# NLQHD-SATA_Front_Panel_Rev1.net
KiCad netlist of a schematic drawn in EAGLE
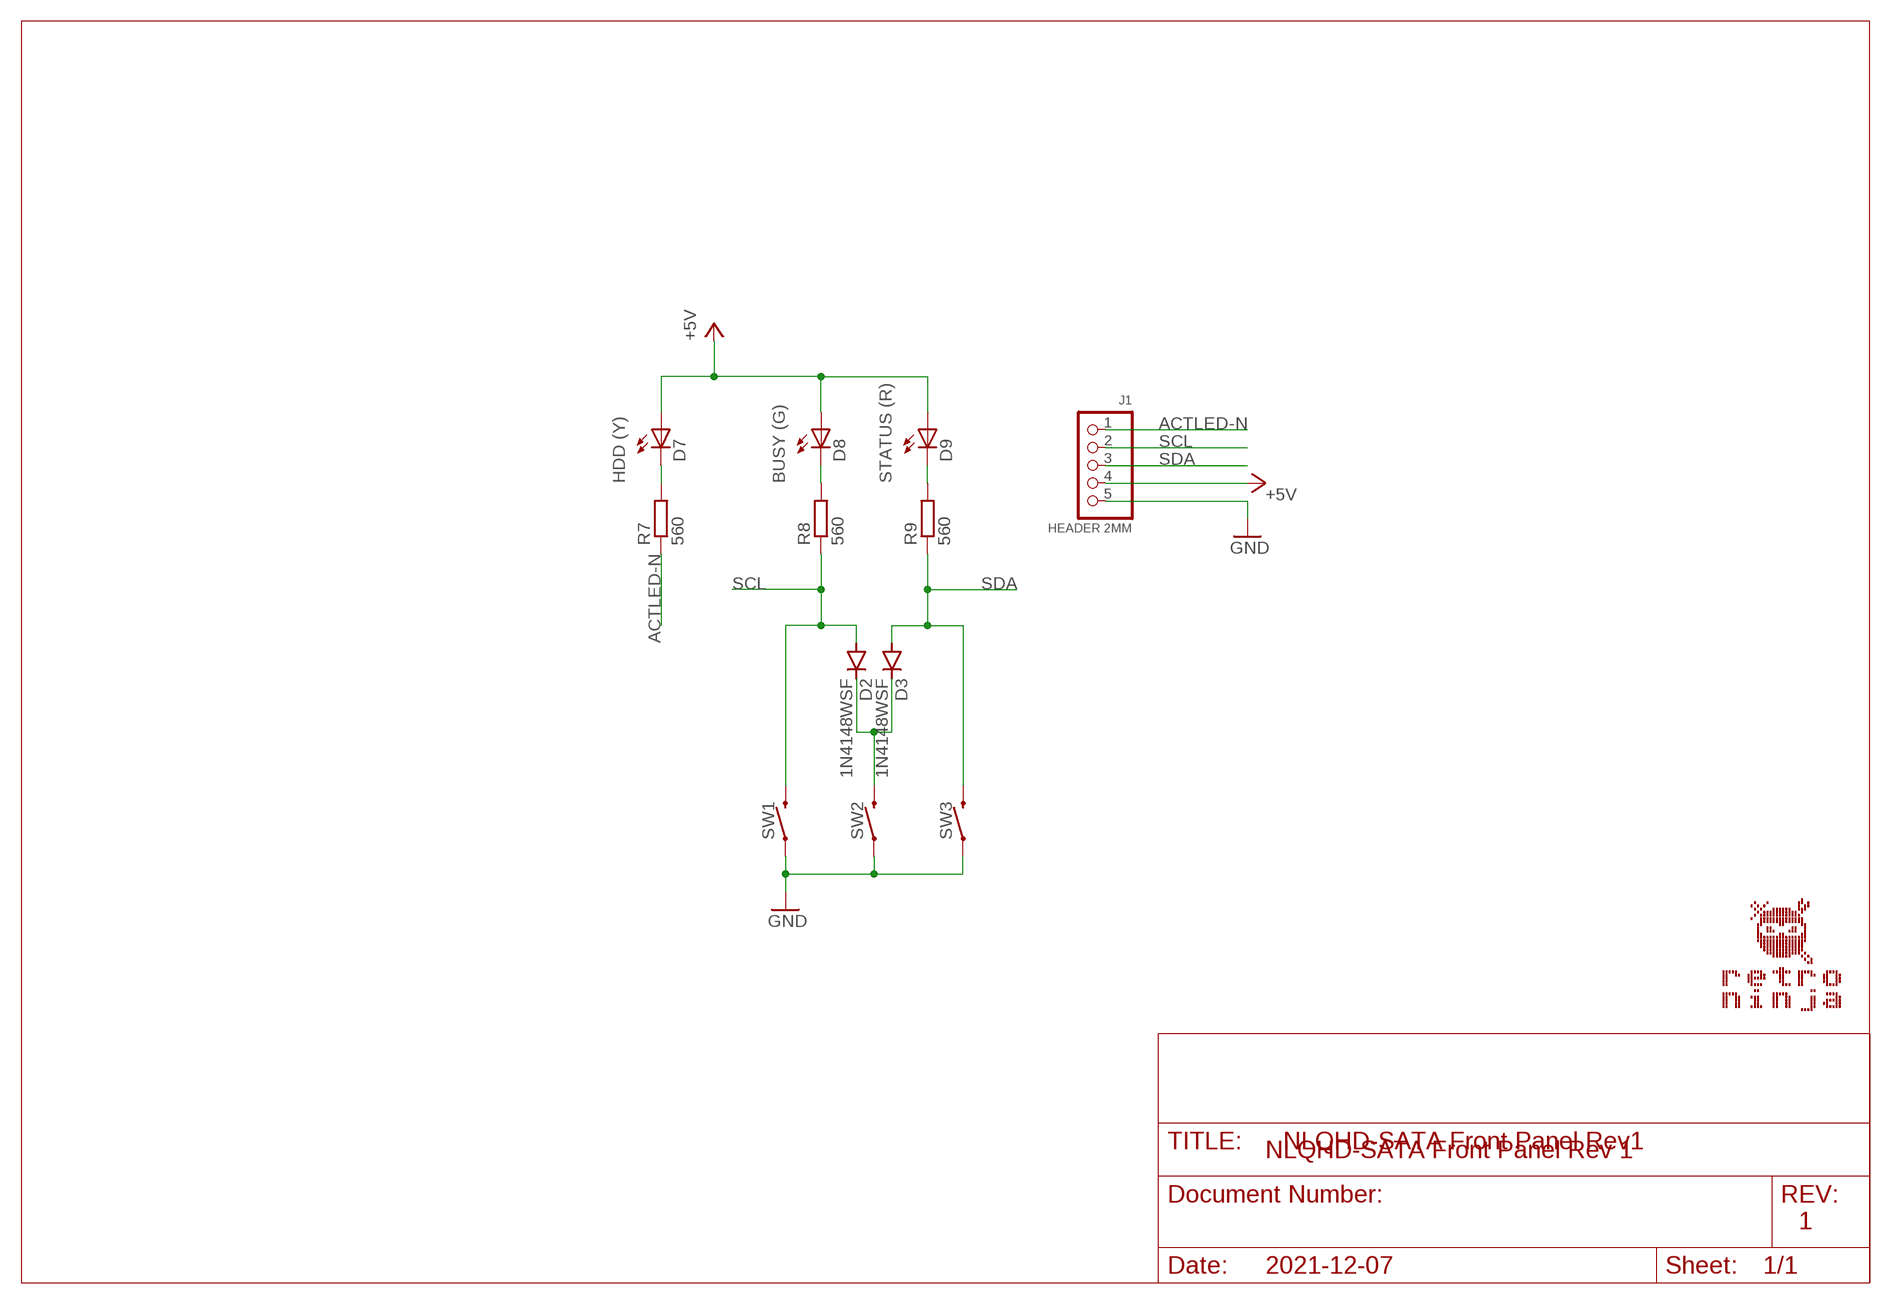
[diagram p0: schematic, sheet 1]

(export (version "E")
  (design (tool "Eeschema 10.0.6"))
  (components
    (comp (ref "D2")
      (value "1N4148WSF")
      (footprint "eagle-import:SOD-323F")
      (libsource (lib "eagle-import") (part "DIODE_SOD-323F"))
    )
    (comp (ref "D3")
      (value "1N4148WSF")
      (footprint "eagle-import:SOD-323F")
      (libsource (lib "eagle-import") (part "DIODE_SOD-323F"))
    )
    (comp (ref "D7")
      (value "LED_3MM_RED")
      (footprint "eagle-import:LED3MM_RED")
      (libsource (lib "eagle-import") (part "LED_3MM_RED"))
    )
    (comp (ref "D8")
      (value "LED_3MM_GREEN")
      (footprint "eagle-import:LED3MM_GREEN")
      (libsource (lib "eagle-import") (part "LED_3MM_GREEN"))
    )
    (comp (ref "D9")
      (value "LED_3MM_GREEN")
      (footprint "eagle-import:LED3MM_GREEN")
      (libsource (lib "eagle-import") (part "LED_3MM_GREEN"))
    )
    (comp (ref "J1")
      (value "HEADER 2MM")
      (footprint "eagle-import:HEADER_1X5_2MM_JST")
      (libsource (lib "eagle-import") (part "HEADER_1X5_2MM_JST"))
    )
    (comp (ref "R7")
      (value "560")
      (footprint "eagle-import:R0805")
      (libsource (lib "eagle-import") (part "R-EU_R0805"))
    )
    (comp (ref "R8")
      (value "560")
      (footprint "eagle-import:R0805")
      (libsource (lib "eagle-import") (part "R-EU_R0805"))
    )
    (comp (ref "R9")
      (value "560")
      (footprint "eagle-import:R0805")
      (libsource (lib "eagle-import") (part "R-EU_R0805"))
    )
    (comp (ref "SW1")
      (value "SWITCH_MOMENTARY_6.0X5.0")
      (footprint "eagle-import:SWITCH_MOM_6.0MMX5.0MM")
      (libsource (lib "eagle-import") (part "SWITCH_MOMENTARY_6.0X5.0"))
    )
    (comp (ref "SW2")
      (value "SWITCH_MOMENTARY_6.0X5.0")
      (footprint "eagle-import:SWITCH_MOM_6.0MMX5.0MM")
      (libsource (lib "eagle-import") (part "SWITCH_MOMENTARY_6.0X5.0"))
    )
    (comp (ref "SW3")
      (value "SWITCH_MOMENTARY_6.0X5.0")
      (footprint "eagle-import:SWITCH_MOM_6.0MMX5.0MM")
      (libsource (lib "eagle-import") (part "SWITCH_MOMENTARY_6.0X5.0"))
    )
  )
  (nets
    (net (code "1") (name "+5V") (class "Default")
      (node (ref "D7") (pin "A") (pinfunction "A_A") (pintype "passive"))
      (node (ref "D8") (pin "A") (pinfunction "A_A") (pintype "passive"))
      (node (ref "D9") (pin "A") (pinfunction "A_A") (pintype "passive"))
      (node (ref "J1") (pin "4") (pinfunction "4_4") (pintype "passive"))
    )
    (net (code "2") (name "/ACTLED-N") (class "Default")
      (node (ref "J1") (pin "1") (pinfunction "1_1") (pintype "passive"))
      (node (ref "R7") (pin "1") (pinfunction "1_1") (pintype "passive"))
    )
    (net (code "3") (name "/SCL") (class "Default")
      (node (ref "D2") (pin "A") (pinfunction "A_A") (pintype "passive"))
      (node (ref "J1") (pin "2") (pinfunction "2_2") (pintype "passive"))
      (node (ref "R8") (pin "1") (pinfunction "1_1") (pintype "passive"))
      (node (ref "SW1") (pin "3") (pinfunction "2_3") (pintype "passive"))
      (node (ref "SW1") (pin "4") (pinfunction "2_4") (pintype "passive"))
    )
    (net (code "4") (name "/SDA") (class "Default")
      (node (ref "D3") (pin "A") (pinfunction "A_A") (pintype "passive"))
      (node (ref "J1") (pin "3") (pinfunction "3_3") (pintype "passive"))
      (node (ref "R9") (pin "1") (pinfunction "1_1") (pintype "passive"))
      (node (ref "SW3") (pin "3") (pinfunction "2_3") (pintype "passive"))
      (node (ref "SW3") (pin "4") (pinfunction "2_4") (pintype "passive"))
    )
    (net (code "5") (name "GND") (class "Default")
      (node (ref "J1") (pin "5") (pinfunction "5_5") (pintype "passive"))
      (node (ref "SW1") (pin "1") (pinfunction "1_1") (pintype "passive"))
      (node (ref "SW1") (pin "2") (pinfunction "1_2") (pintype "passive"))
      (node (ref "SW2") (pin "1") (pinfunction "1_1") (pintype "passive"))
      (node (ref "SW2") (pin "2") (pinfunction "1_2") (pintype "passive"))
      (node (ref "SW3") (pin "1") (pinfunction "1_1") (pintype "passive"))
      (node (ref "SW3") (pin "2") (pinfunction "1_2") (pintype "passive"))
    )
    (net (code "6") (name "Net-(D2-PadC)") (class "Default")
      (node (ref "D2") (pin "C") (pinfunction "C_C") (pintype "passive"))
      (node (ref "D3") (pin "C") (pinfunction "C_C") (pintype "passive"))
      (node (ref "SW2") (pin "3") (pinfunction "2_3") (pintype "passive"))
      (node (ref "SW2") (pin "4") (pinfunction "2_4") (pintype "passive"))
    )
    (net (code "7") (name "Net-(D7-C)") (class "Default")
      (node (ref "D7") (pin "K") (pinfunction "C_K") (pintype "passive"))
      (node (ref "R7") (pin "2") (pinfunction "2_2") (pintype "passive"))
    )
    (net (code "8") (name "Net-(D8-C)") (class "Default")
      (node (ref "D8") (pin "K") (pinfunction "C_K") (pintype "passive"))
      (node (ref "R8") (pin "2") (pinfunction "2_2") (pintype "passive"))
    )
    (net (code "9") (name "Net-(D9-C)") (class "Default")
      (node (ref "D9") (pin "K") (pinfunction "C_K") (pintype "passive"))
      (node (ref "R9") (pin "2") (pinfunction "2_2") (pintype "passive"))
    )
  )
)
